# 3_ADSTM32-Peripheral.net
KiCad netlist of a schematic drawn in Altium Designer
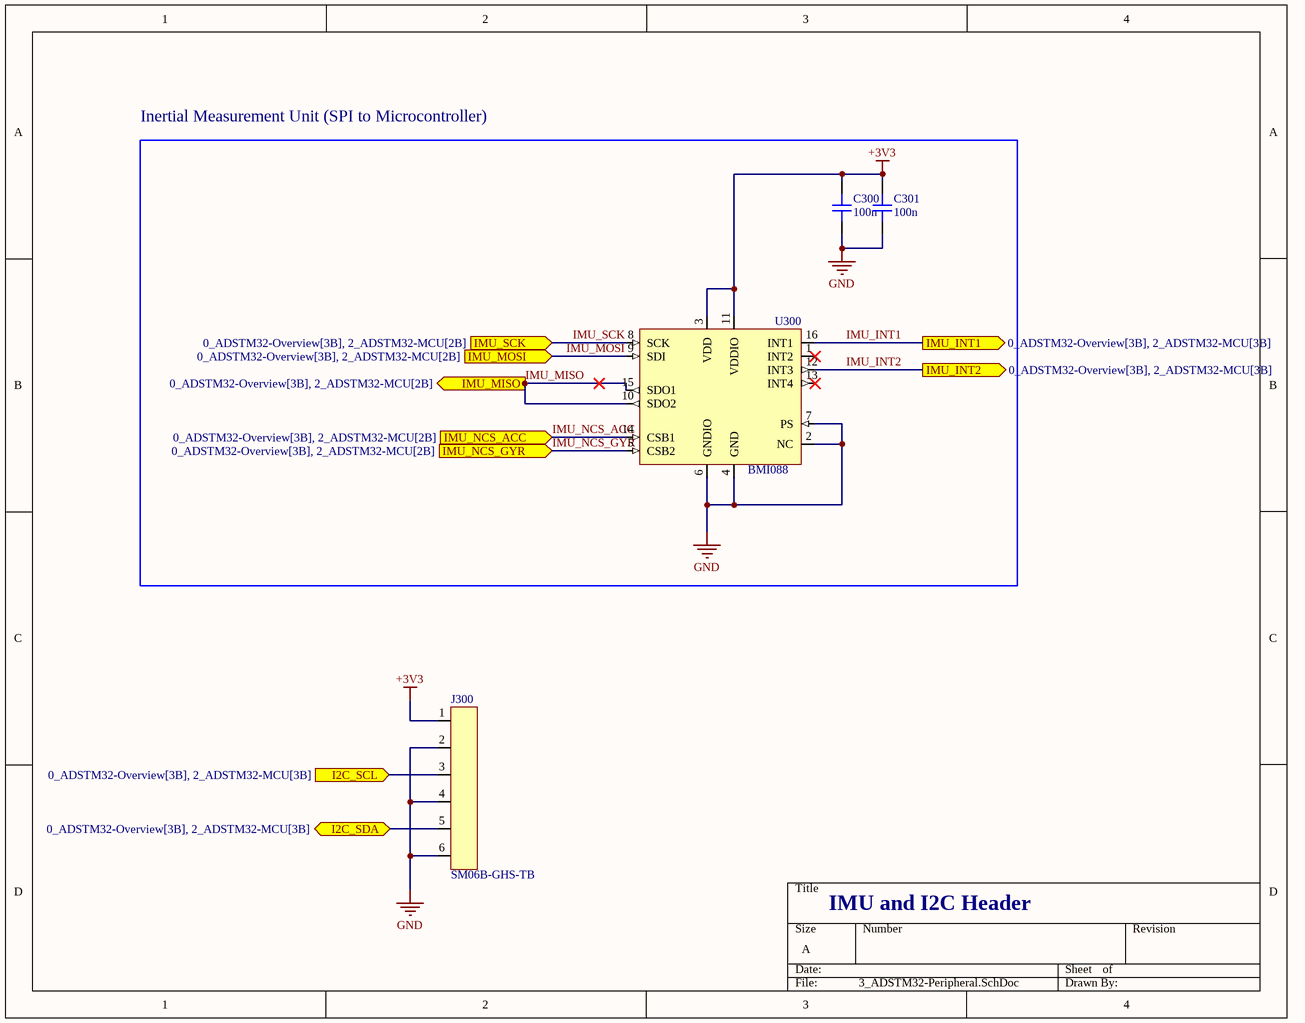
[diagram p0:  3_ADSTM32-Peripheral.SchDoc]

(export (version "E")
  (design (tool "Eeschema 10.0.6"))
  (components
    (comp (ref "C300")
      (value "100n")
      (footprint "CAP_0603")
      (description "Capaictor SMD 0603 Generic")
      (libsource (lib "Schematic-Lib-KEM") (part "CAP_0603"))
    )
    (comp (ref "C301")
      (value "100n")
      (footprint "CAP_0603")
      (description "Capaictor SMD 0603 Generic")
      (libsource (lib "Schematic-Lib-KEM") (part "CAP_0603"))
    )
    (comp (ref "J300")
      (value "SM06B-GHS-TB")
      (footprint "SM06B-GHS-TB")
      (description "Header Connector 6 Position 1.25MM Pitch SMD Horizontal JST GH")
      (fields (field (name "MANUFACTURER") "JST"))
      (libsource (lib "Schematic-Lib-KEM") (part "SM06B-GHS-TB"))
    )
    (comp (ref "U300")
      (value "BMI088")
      (footprint "BMI088")
      (description "Inertial Measurement Unit (IMU) 6-axis 16bit")
      (fields (field (name "MANUFACTURER") "Bosch"))
      (libsource (lib "Schematic-Lib-KEM") (part "BMI088"))
    )
  )
  (nets
    (net (code "1") (name "+3V3") (class "Default")
      (node (ref "C300") (pin "2") (pintype "passive"))
      (node (ref "C301") (pin "2") (pintype "passive"))
      (node (ref "J300") (pin "1") (pintype "passive"))
      (node (ref "U300") (pin "11") (pinfunction "VDDIO_11") (pintype "power_in"))
      (node (ref "U300") (pin "3") (pinfunction "VDD_3") (pintype "power_in"))
    )
    (net (code "2") (name "/I2C_SCL") (class "Default") (node (ref "J300") (pin "3") (pintype "passive")))
    (net (code "3") (name "/I2C_SDA") (class "Default") (node (ref "J300") (pin "5") (pintype "passive")))
    (net (code "4") (name "/IMU_INT1") (class "Default")
      (node (ref "U300") (pin "16") (pinfunction "INT1_16") (pintype "bidirectional"))
    )
    (net (code "5") (name "/IMU_INT2") (class "Default")
      (node (ref "U300") (pin "12") (pinfunction "INT3_12") (pintype "output"))
    )
    (net (code "6") (name "/IMU_MISO") (class "Default")
      (node (ref "U300") (pin "10") (pinfunction "SDO2_10") (pintype "output"))
      (node (ref "U300") (pin "15") (pinfunction "SDO1_15") (pintype "output"))
    )
    (net (code "7") (name "/IMU_MOSI") (class "Default")
      (node (ref "U300") (pin "9") (pinfunction "SDI_9") (pintype "input"))
    )
    (net (code "8") (name "/IMU_NCS_ACC") (class "Default")
      (node (ref "U300") (pin "14") (pinfunction "CSB1_14") (pintype "input"))
    )
    (net (code "9") (name "/IMU_NCS_GYR") (class "Default")
      (node (ref "U300") (pin "5") (pinfunction "CSB2_5") (pintype "input"))
    )
    (net (code "10") (name "/IMU_SCK") (class "Default")
      (node (ref "U300") (pin "8") (pinfunction "SCK_8") (pintype "input"))
    )
    (net (code "11") (name "GND") (class "Default")
      (node (ref "C300") (pin "1") (pintype "passive"))
      (node (ref "C301") (pin "1") (pintype "passive"))
      (node (ref "J300") (pin "2") (pintype "passive"))
      (node (ref "J300") (pin "4") (pintype "passive"))
      (node (ref "J300") (pin "6") (pintype "passive"))
      (node (ref "U300") (pin "2") (pinfunction "NC_2") (pintype "passive"))
      (node (ref "U300") (pin "4") (pinfunction "GND_4") (pintype "power_in"))
      (node (ref "U300") (pin "6") (pinfunction "GNDIO_6") (pintype "power_in"))
      (node (ref "U300") (pin "7") (pinfunction "PS_7") (pintype "input"))
    )
    (net (code "12") (name "unconnected-(U300-INT2-Pad1)") (class "Default")
      (node (ref "U300") (pin "1") (pinfunction "INT2_1") (pintype "bidirectional+no_connect"))
    )
    (net (code "13") (name "unconnected-(U300-INT4-Pad13)") (class "Default")
      (node (ref "U300") (pin "13") (pinfunction "INT4_13") (pintype "output+no_connect"))
    )
  )
)
